# design.net
KiCad netlist of a schematic drawn in EasyEDA Pro
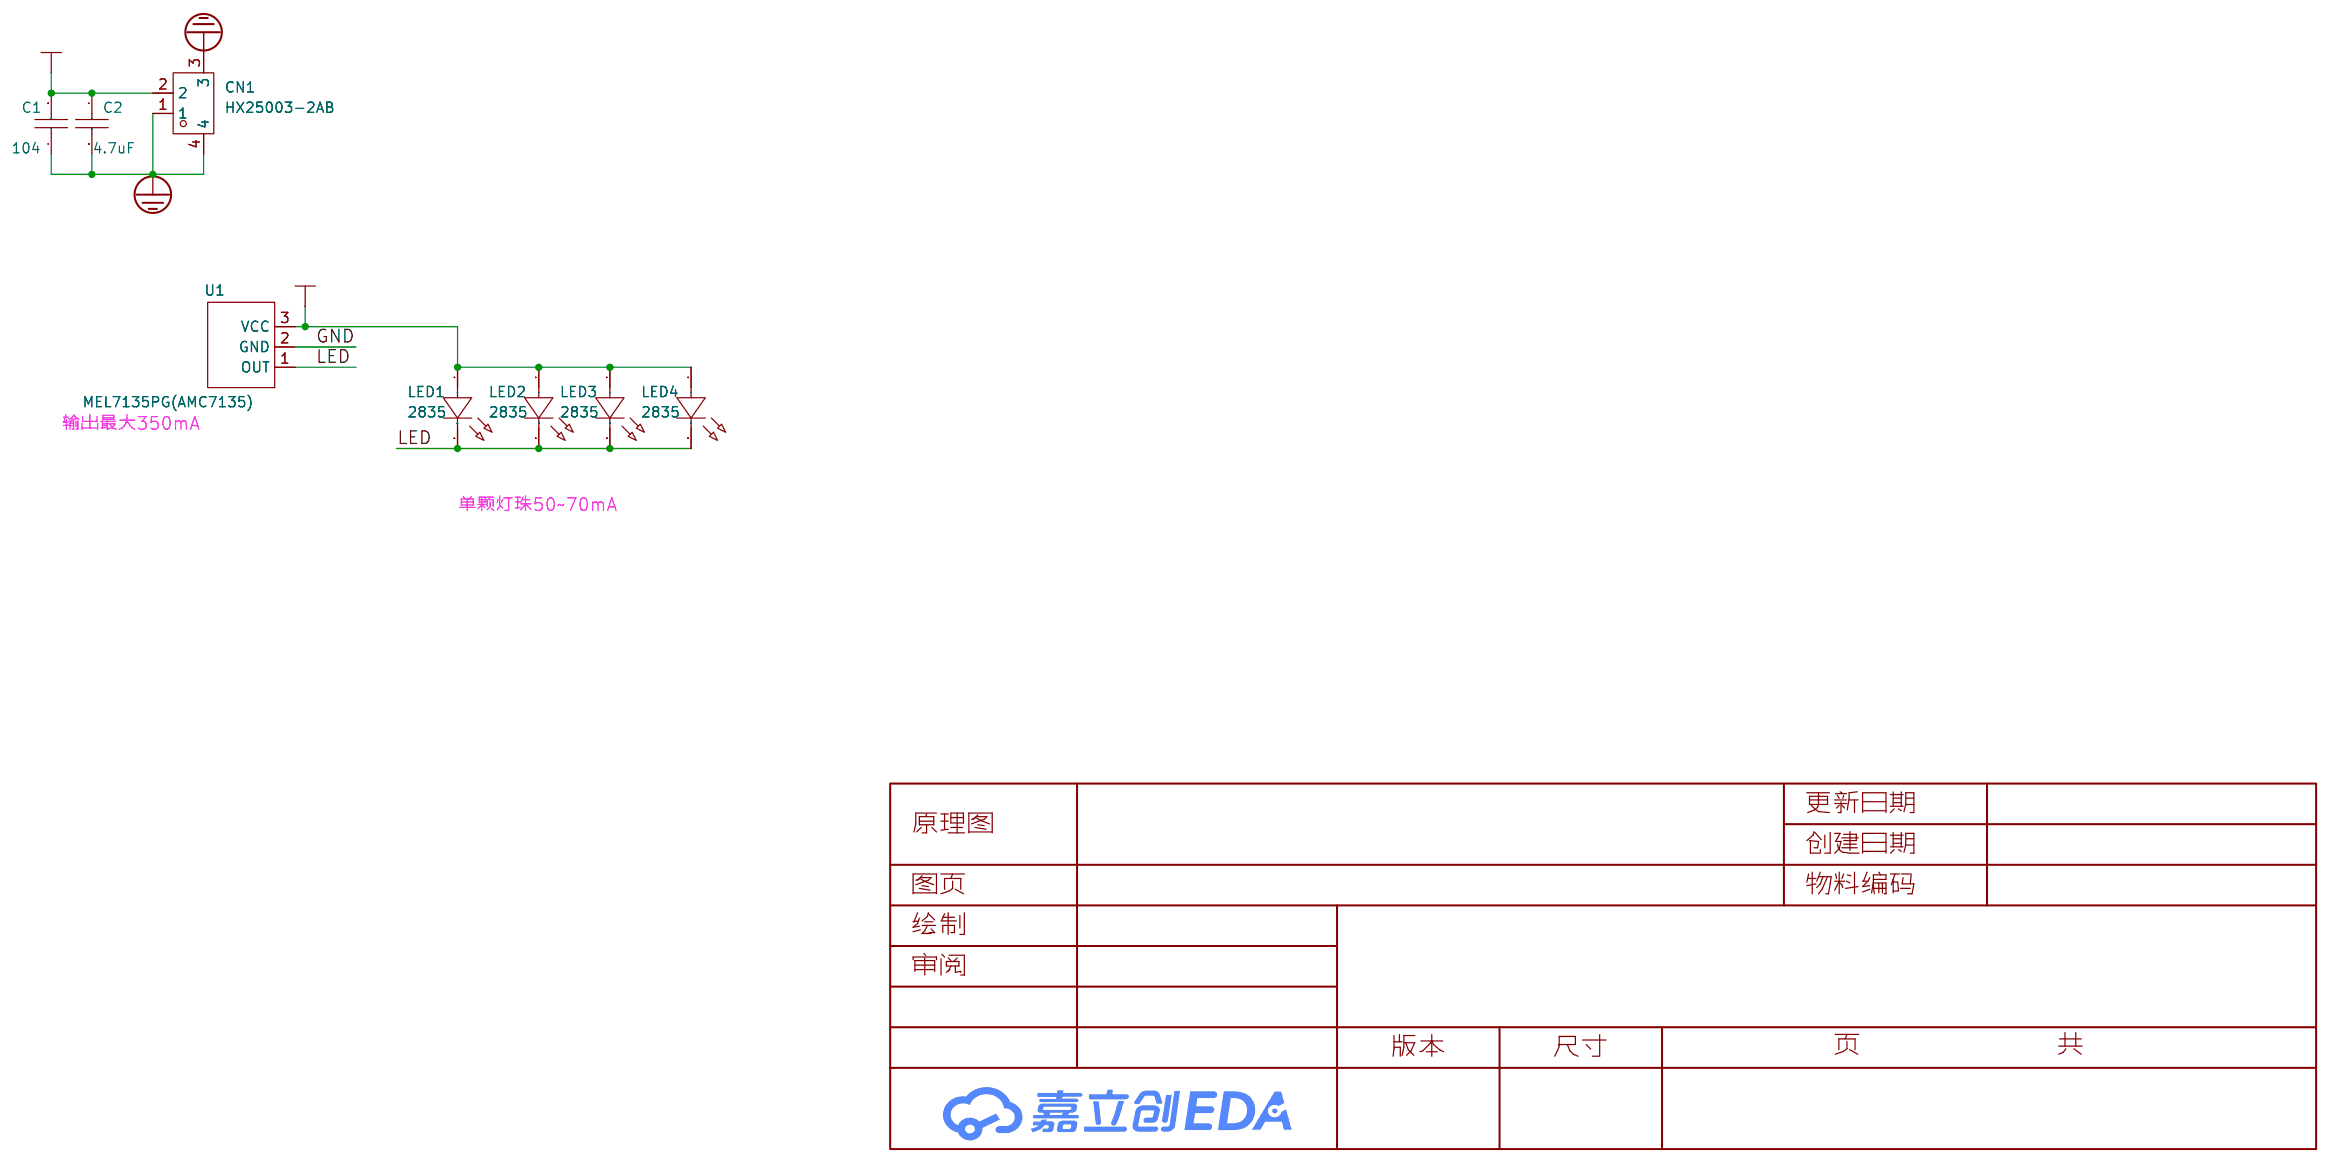
[diagram p0: schematic sheet]

(export (version "E")
  (design (tool "Eeschema 10.0.6"))
  (components
    (comp (ref "C1")
      (value "104")
      (footprint "easyedapro:0603C")
      (description "Capacitor (Semiconductor SIM Model)")
      (libsource (lib "easyedapro") (part "Cap Semi"))
    )
    (comp (ref "C2") (value "4.7uF") (libsource (lib "easyedapro") (part "CAP")))
    (comp (ref "CN1")
      (value "HX25003-2AB")
      (footprint "easyedapro:CONN-SMD_P2.50_HX25003-2AB")
      (fields (field (name "Manufacturer") "HX(红星)"))
      (libsource (lib "easyedapro") (part "HX25003-2AB"))
    )
    (comp (ref "LED1")
      (value "2835")
      (footprint "easyedapro:LED-SMD_L3.5-W2.8_2835")
      (libsource (lib "easyedapro") (part "2835"))
    )
    (comp (ref "LED2")
      (value "2835")
      (footprint "easyedapro:LED-SMD_L3.5-W2.8_2835")
      (libsource (lib "easyedapro") (part "2835"))
    )
    (comp (ref "LED3")
      (value "2835")
      (footprint "easyedapro:LED-SMD_L3.5-W2.8_2835")
      (libsource (lib "easyedapro") (part "2835"))
    )
    (comp (ref "LED4")
      (value "2835")
      (footprint "easyedapro:LED-SMD_L3.5-W2.8_2835")
      (libsource (lib "easyedapro") (part "2835"))
    )
    (comp (ref "U1")
      (value "MEL7135PG(AMC7135)")
      (footprint "easyedapro:SOT-89-3_L4.5-W2.5-P1.50-LS4.2-BR")
      (description "类型:-;工作电压(DC):2.7V~6V;开关频率:-;通道数:1;输出电压:-;输出电流:350mA;调光:-;拓扑结构:-;")
      (fields (field (name "Manufacturer") "MICRONE(南京微盟)"))
      (libsource (lib "easyedapro") (part "MEL7135PG"))
    )
  )
  (nets
    (net (code "1") (name "/LED") (class "Default")
      (node (ref "LED1") (pin "2") (pinfunction "C_2") (pintype "unspecified"))
      (node (ref "LED2") (pin "2") (pinfunction "C_2") (pintype "unspecified"))
      (node (ref "LED3") (pin "2") (pinfunction "C_2") (pintype "unspecified"))
      (node (ref "LED4") (pin "2") (pinfunction "C_2") (pintype "unspecified"))
      (node (ref "U1") (pin "1") (pinfunction "OUT_1") (pintype "unspecified"))
    )
    (net (code "2") (name "5V_VCC") (class "Default")
      (node (ref "C1") (pin "2") (pinfunction "2_2") (pintype "unspecified"))
      (node (ref "C2") (pin "1") (pinfunction "1_1") (pintype "input"))
      (node (ref "CN1") (pin "2") (pinfunction "2_2") (pintype "unspecified"))
      (node (ref "LED1") (pin "1") (pinfunction "A_1") (pintype "unspecified"))
      (node (ref "LED2") (pin "1") (pinfunction "A_1") (pintype "unspecified"))
      (node (ref "LED3") (pin "1") (pinfunction "A_1") (pintype "unspecified"))
      (node (ref "LED4") (pin "1") (pinfunction "A_1") (pintype "unspecified"))
      (node (ref "U1") (pin "3") (pinfunction "VCC_3") (pintype "unspecified"))
    )
    (net (code "3") (name "GND") (class "Default")
      (node (ref "C1") (pin "1") (pinfunction "1_1") (pintype "unspecified"))
      (node (ref "C2") (pin "2") (pinfunction "2_2") (pintype "input"))
      (node (ref "CN1") (pin "1") (pinfunction "1_1") (pintype "unspecified"))
      (node (ref "CN1") (pin "3") (pinfunction "3_3") (pintype "unspecified"))
      (node (ref "CN1") (pin "4") (pinfunction "4_4") (pintype "unspecified"))
      (node (ref "U1") (pin "2") (pinfunction "GND_2") (pintype "unspecified"))
    )
  )
)
